# FeatherTPL5010.net
KiCad netlist of a schematic drawn in EAGLE
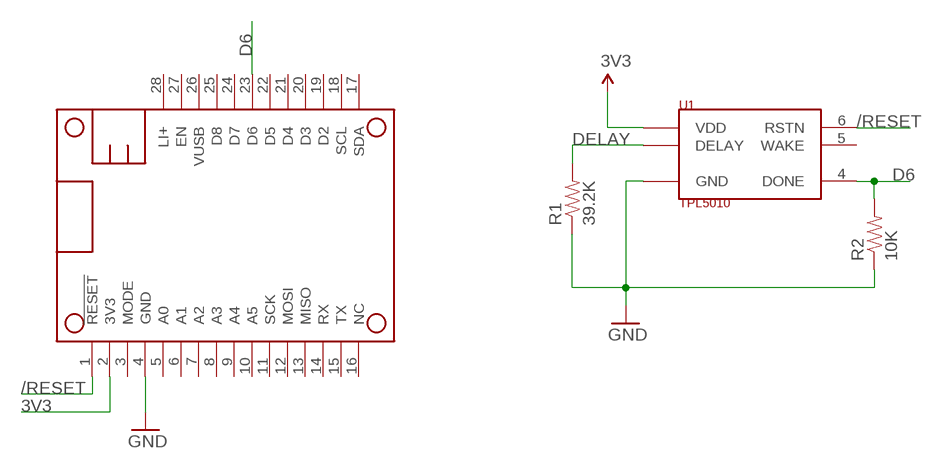
[diagram p0: schematic, sheet 1]

(export (version "E")
  (design (tool "Eeschema 10.0.6"))
  (components
    (comp (ref "MS1")
      (value "FEATHERWING_NODIM")
      (footprint "eagle-import:FEATHERWING_NODIM")
      (libsource (lib "eagle-import") (part "FEATHERWING_NODIM"))
    )
    (comp (ref "R1")
      (value "39.2K")
      (footprint "eagle-import:0603-RES")
      (libsource (lib "eagle-import") (part "RES-39.2K-0603"))
    )
    (comp (ref "R2")
      (value "10K")
      (footprint "eagle-import:0603-RES")
      (libsource (lib "eagle-import") (part "RES-10K-06030603"))
    )
    (comp (ref "U1")
      (value "TPL5010")
      (footprint "eagle-import:SOT-23-6-TI")
      (libsource (lib "eagle-import") (part "TPL5010"))
    )
  )
  (nets
    (net (code "1") (name "/D6") (class "Default")
      (node (ref "MS1") (pin "23") (pinfunction "D6_23") (pintype "bidirectional"))
      (node (ref "R2") (pin "2") (pinfunction "2_2") (pintype "passive"))
      (node (ref "U1") (pin "4") (pinfunction "DONE_4") (pintype "input"))
    )
    (net (code "2") (name "/DELAY") (class "Default")
      (node (ref "R1") (pin "2") (pinfunction "2_2") (pintype "passive"))
      (node (ref "U1") (pin "3") (pinfunction "DELAY_3") (pintype "input"))
    )
    (net (code "3") (name "/LI+") (class "Default")
      (node (ref "MS1") (pin "28") (pinfunction "LI+_28") (pintype "power_in"))
    )
    (net (code "4") (name "/VUSB") (class "Default")
      (node (ref "MS1") (pin "26") (pinfunction "VUSB_26") (pintype "power_in"))
    )
    (net (code "5") (name "/{slash}RESET") (class "Default")
      (node (ref "MS1") (pin "1") (pinfunction "~{RESET}_1") (pintype "input"))
      (node (ref "U1") (pin "6") (pinfunction "RSTN_6") (pintype "open_collector"))
    )
    (net (code "6") (name "3V3") (class "Default")
      (node (ref "MS1") (pin "2") (pinfunction "3V3_2") (pintype "power_in"))
      (node (ref "U1") (pin "1") (pinfunction "VDD_1") (pintype "passive"))
    )
    (net (code "7") (name "GND") (class "Default")
      (node (ref "MS1") (pin "4") (pinfunction "GND_4") (pintype "power_in"))
      (node (ref "R1") (pin "1") (pinfunction "1_1") (pintype "passive"))
      (node (ref "R2") (pin "1") (pinfunction "1_1") (pintype "passive"))
      (node (ref "U1") (pin "2") (pinfunction "GND_2") (pintype "passive"))
    )
    (net (code "8") (name "unconnected-(MS1-A0-Pad5)") (class "Default")
      (node (ref "MS1") (pin "5") (pinfunction "A0_5") (pintype "bidirectional"))
    )
    (net (code "9") (name "unconnected-(MS1-A1-Pad6)") (class "Default")
      (node (ref "MS1") (pin "6") (pinfunction "A1_6") (pintype "bidirectional"))
    )
    (net (code "10") (name "unconnected-(MS1-A2-Pad7)") (class "Default")
      (node (ref "MS1") (pin "7") (pinfunction "A2_7") (pintype "bidirectional"))
    )
    (net (code "11") (name "unconnected-(MS1-A3-Pad8)") (class "Default")
      (node (ref "MS1") (pin "8") (pinfunction "A3_8") (pintype "bidirectional"))
    )
    (net (code "12") (name "unconnected-(MS1-A4-Pad9)") (class "Default")
      (node (ref "MS1") (pin "9") (pinfunction "A4_9") (pintype "bidirectional"))
    )
    (net (code "13") (name "unconnected-(MS1-A5-Pad10)") (class "Default")
      (node (ref "MS1") (pin "10") (pinfunction "A5_10") (pintype "bidirectional"))
    )
    (net (code "14") (name "unconnected-(MS1-D2-Pad19)") (class "Default")
      (node (ref "MS1") (pin "19") (pinfunction "D2_19") (pintype "bidirectional"))
    )
    (net (code "15") (name "unconnected-(MS1-D3-Pad20)") (class "Default")
      (node (ref "MS1") (pin "20") (pinfunction "D3_20") (pintype "bidirectional"))
    )
    (net (code "16") (name "unconnected-(MS1-D4-Pad21)") (class "Default")
      (node (ref "MS1") (pin "21") (pinfunction "D4_21") (pintype "bidirectional"))
    )
    (net (code "17") (name "unconnected-(MS1-D5-Pad22)") (class "Default")
      (node (ref "MS1") (pin "22") (pinfunction "D5_22") (pintype "bidirectional"))
    )
    (net (code "18") (name "unconnected-(MS1-D7-Pad24)") (class "Default")
      (node (ref "MS1") (pin "24") (pinfunction "D7_24") (pintype "bidirectional"))
    )
    (net (code "19") (name "unconnected-(MS1-D8-Pad25)") (class "Default")
      (node (ref "MS1") (pin "25") (pinfunction "D8_25") (pintype "bidirectional"))
    )
    (net (code "20") (name "unconnected-(MS1-EN-Pad27)") (class "Default")
      (node (ref "MS1") (pin "27") (pinfunction "EN_27") (pintype "passive"))
    )
    (net (code "21") (name "unconnected-(MS1-MISO-Pad13)") (class "Default")
      (node (ref "MS1") (pin "13") (pinfunction "MISO_13") (pintype "bidirectional"))
    )
    (net (code "22") (name "unconnected-(MS1-MODE-Pad3)") (class "Default")
      (node (ref "MS1") (pin "3") (pinfunction "MODE_3") (pintype "passive"))
    )
    (net (code "23") (name "unconnected-(MS1-MOSI-Pad12)") (class "Default")
      (node (ref "MS1") (pin "12") (pinfunction "MOSI_12") (pintype "bidirectional"))
    )
    (net (code "24") (name "unconnected-(MS1-NC-Pad16)") (class "Default")
      (node (ref "MS1") (pin "16") (pinfunction "NC_16") (pintype "passive"))
    )
    (net (code "25") (name "unconnected-(MS1-RX-Pad14)") (class "Default")
      (node (ref "MS1") (pin "14") (pinfunction "RX_14") (pintype "bidirectional"))
    )
    (net (code "26") (name "unconnected-(MS1-SCK-Pad11)") (class "Default")
      (node (ref "MS1") (pin "11") (pinfunction "SCK_11") (pintype "bidirectional"))
    )
    (net (code "27") (name "unconnected-(MS1-SCL-Pad18)") (class "Default")
      (node (ref "MS1") (pin "18") (pinfunction "SCL_18") (pintype "bidirectional"))
    )
    (net (code "28") (name "unconnected-(MS1-SDA-Pad17)") (class "Default")
      (node (ref "MS1") (pin "17") (pinfunction "SDA_17") (pintype "bidirectional"))
    )
    (net (code "29") (name "unconnected-(MS1-TX-Pad15)") (class "Default")
      (node (ref "MS1") (pin "15") (pinfunction "TX_15") (pintype "bidirectional"))
    )
    (net (code "30") (name "unconnected-(U1-WAKE-Pad5)") (class "Default")
      (node (ref "U1") (pin "5") (pinfunction "WAKE_5") (pintype "output"))
    )
  )
)
